# final.net
KiCad netlist of a schematic drawn in EAGLE
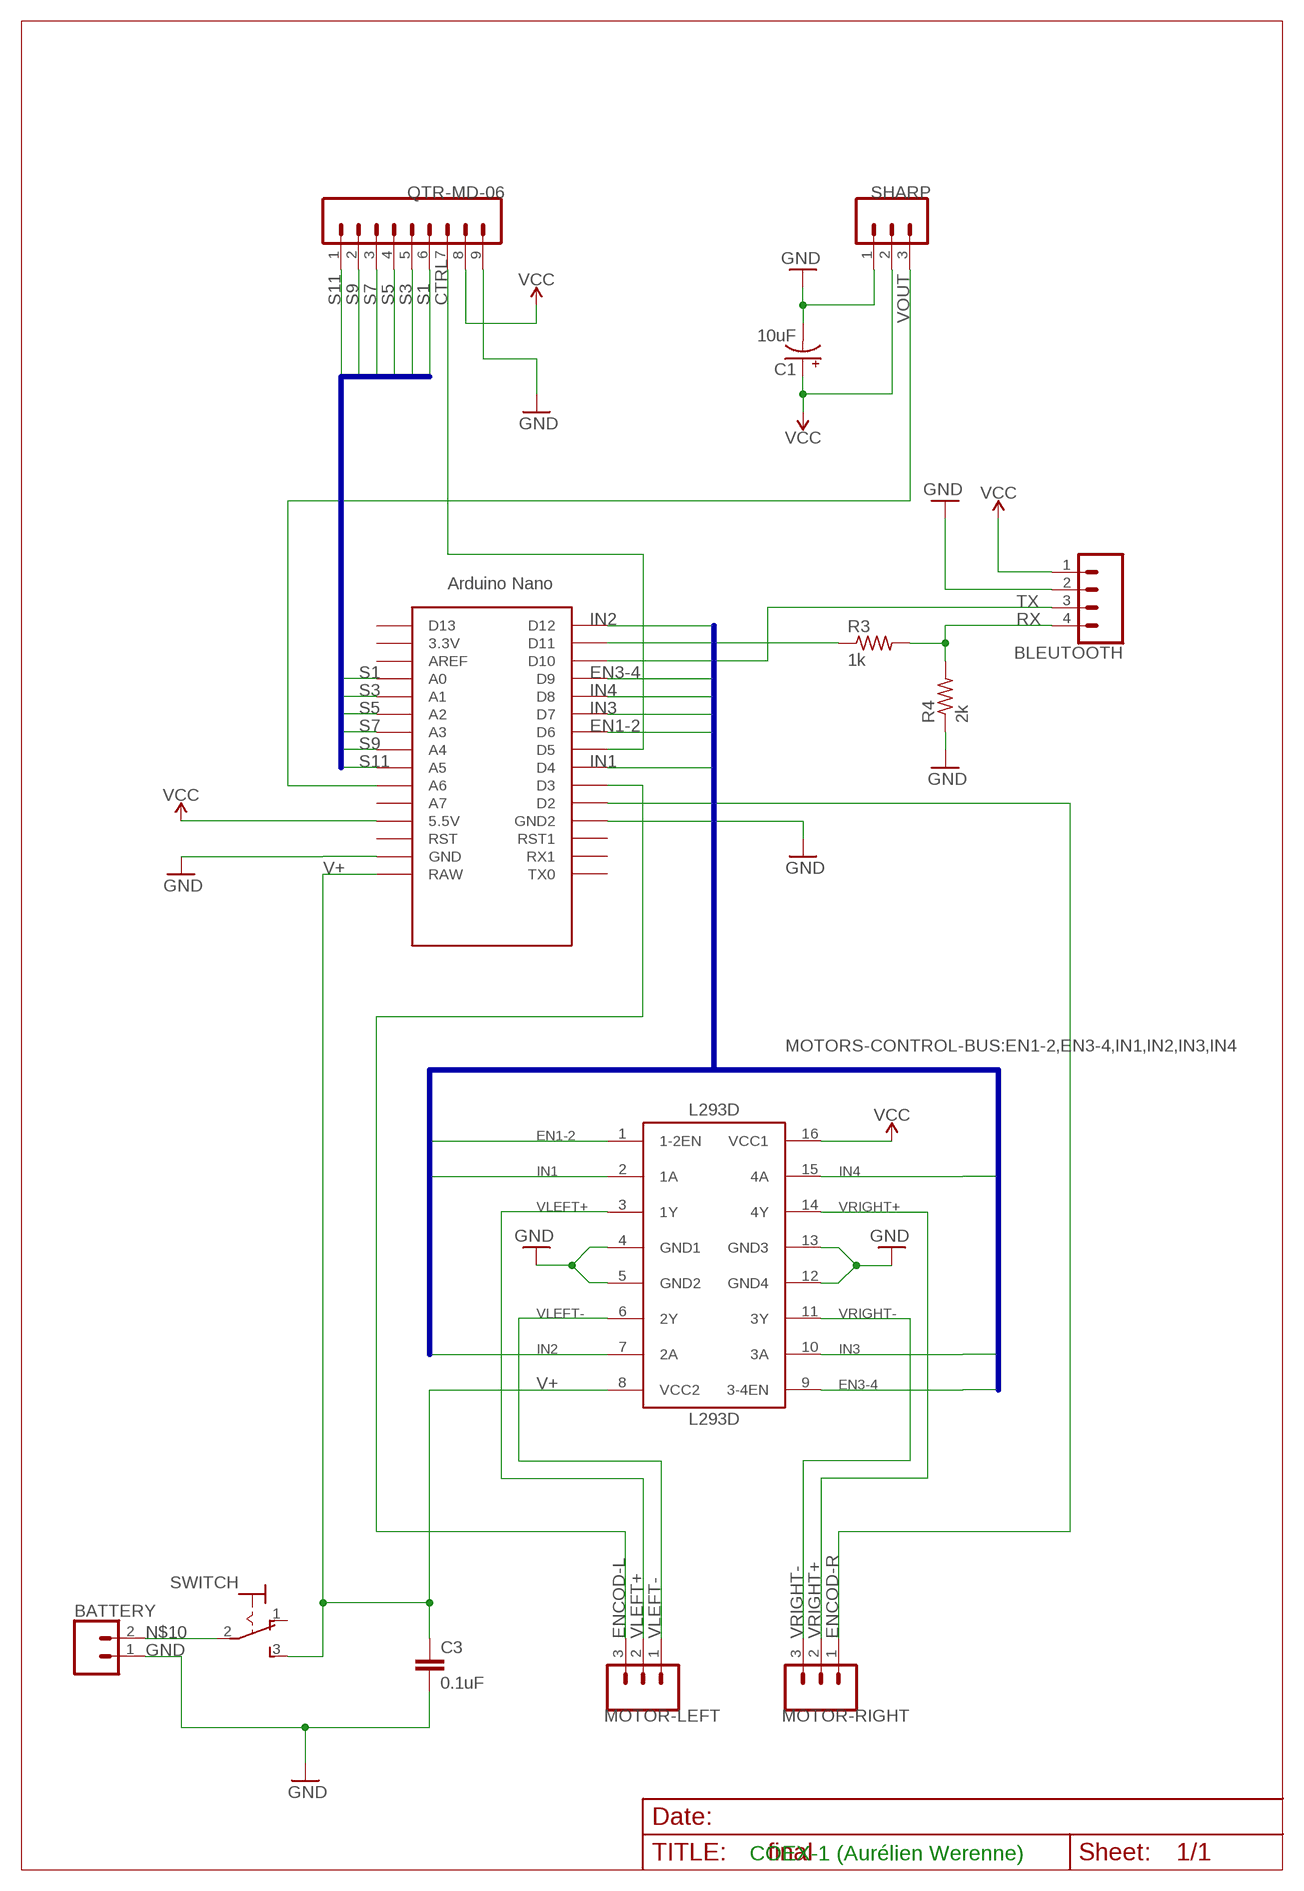
[diagram p0: schematic, sheet 1]

(export (version "E")
  (design (tool "Eeschema 10.0.6"))
  (components
    (comp (ref "BATTERY")
      (value "CONN_02")
      (footprint "eagle-import:1X02")
      (libsource (lib "eagle-import") (part "CONN_02"))
    )
    (comp (ref "BLEUTOOTH")
      (value "CONN_04")
      (footprint "eagle-import:1X04")
      (libsource (lib "eagle-import") (part "CONN_04"))
    )
    (comp (ref "C1")
      (value "10uF")
      (footprint "eagle-import:CPOL-RADIAL-2.5MM-5MM")
      (libsource (lib "eagle-import") (part "10UF-POLAR-RADIAL-2.5MM-25V-20%"))
    )
    (comp (ref "C3")
      (value "0.1uF")
      (footprint "eagle-import:CAP-PTH-SMALL-KIT")
      (libsource (lib "eagle-import") (part "0.1UF-KIT-EZ-50V-20%"))
    )
    (comp (ref "L293D")
      (value "L293D")
      (footprint "eagle-import:DIL16")
      (libsource (lib "eagle-import") (part "L293D"))
    )
    (comp (ref "MOTOR-LEFT")
      (value "CONN_03")
      (footprint "eagle-import:1X03")
      (libsource (lib "eagle-import") (part "CONN_03"))
    )
    (comp (ref "MOTOR-RIGHT")
      (value "CONN_03")
      (footprint "eagle-import:1X03")
      (libsource (lib "eagle-import") (part "CONN_03"))
    )
    (comp (ref "QTR-MD-06")
      (value "CONN_09")
      (footprint "eagle-import:1X09")
      (libsource (lib "eagle-import") (part "CONN_09"))
    )
    (comp (ref "R3")
      (value "1k")
      (footprint "eagle-import:0207_12")
      (libsource (lib "eagle-import") (part "R-US_0207/12"))
    )
    (comp (ref "R4")
      (value "2k")
      (footprint "eagle-import:0207_12")
      (libsource (lib "eagle-import") (part "R-US_0207/12"))
    )
    (comp (ref "SHARP")
      (value "CONN_03")
      (footprint "eagle-import:1X03")
      (libsource (lib "eagle-import") (part "CONN_03"))
    )
    (comp (ref "SWITCH")
      (value "320-916")
      (footprint "eagle-import:320-916")
      (libsource (lib "eagle-import") (part "320-916"))
    )
    (comp (ref "U$1")
      (value "NANO")
      (footprint "eagle-import:NANO")
      (libsource (lib "eagle-import") (part "NANO"))
    )
  )
  (nets
    (net (code "2") (name "/CTRL") (class "Default")
      (node (ref "QTR-MD-06") (pin "7") (pinfunction "7_7") (pintype "passive"))
      (node (ref "U$1") (pin "D5") (pinfunction "D5_D5") (pintype "bidirectional"))
    )
    (net (code "3") (name "/EN1-2") (class "Default")
      (node (ref "L293D") (pin "1") (pinfunction "1-2EN_1") (pintype "input"))
      (node (ref "U$1") (pin "D6") (pinfunction "D6_D6") (pintype "bidirectional"))
    )
    (net (code "4") (name "/EN3-4") (class "Default")
      (node (ref "L293D") (pin "9") (pinfunction "3-4EN_9") (pintype "input"))
      (node (ref "U$1") (pin "D9") (pinfunction "D9_D9") (pintype "bidirectional"))
    )
    (net (code "5") (name "/ENCOD-L") (class "Default")
      (node (ref "MOTOR-LEFT") (pin "3") (pinfunction "3_3") (pintype "passive"))
      (node (ref "U$1") (pin "D3") (pinfunction "D3_D3") (pintype "bidirectional"))
    )
    (net (code "6") (name "/ENCOD-R") (class "Default")
      (node (ref "MOTOR-RIGHT") (pin "1") (pinfunction "1_1") (pintype "passive"))
      (node (ref "U$1") (pin "D2") (pinfunction "D2_D2") (pintype "bidirectional"))
    )
    (net (code "7") (name "/IN1") (class "Default")
      (node (ref "L293D") (pin "2") (pinfunction "1A_2") (pintype "input"))
      (node (ref "U$1") (pin "D4") (pinfunction "D4_D4") (pintype "bidirectional"))
    )
    (net (code "8") (name "/IN2") (class "Default")
      (node (ref "L293D") (pin "7") (pinfunction "2A_7") (pintype "input"))
      (node (ref "U$1") (pin "D12") (pinfunction "D12_D12") (pintype "bidirectional"))
    )
    (net (code "9") (name "/IN3") (class "Default")
      (node (ref "L293D") (pin "10") (pinfunction "3A_10") (pintype "input"))
      (node (ref "U$1") (pin "D7") (pinfunction "D7_D7") (pintype "bidirectional"))
    )
    (net (code "10") (name "/IN4") (class "Default")
      (node (ref "L293D") (pin "15") (pinfunction "4A_15") (pintype "input"))
      (node (ref "U$1") (pin "D8") (pinfunction "D8_D8") (pintype "bidirectional"))
    )
    (net (code "11") (name "/N$10") (class "Default")
      (node (ref "BATTERY") (pin "2") (pinfunction "2_2") (pintype "passive"))
      (node (ref "SWITCH") (pin "2") (pinfunction "P_2") (pintype "passive"))
    )
    (net (code "12") (name "/RX") (class "Default")
      (node (ref "BLEUTOOTH") (pin "4") (pinfunction "4_4") (pintype "passive"))
      (node (ref "R3") (pin "2") (pinfunction "2_2") (pintype "passive"))
      (node (ref "R4") (pin "2") (pinfunction "2_2") (pintype "passive"))
    )
    (net (code "13") (name "/S1") (class "Default")
      (node (ref "QTR-MD-06") (pin "6") (pinfunction "6_6") (pintype "passive"))
      (node (ref "U$1") (pin "A0") (pinfunction "A0_A0") (pintype "bidirectional"))
    )
    (net (code "14") (name "/S3") (class "Default")
      (node (ref "QTR-MD-06") (pin "5") (pinfunction "5_5") (pintype "passive"))
      (node (ref "U$1") (pin "A1") (pinfunction "A1_A1") (pintype "bidirectional"))
    )
    (net (code "15") (name "/S5") (class "Default")
      (node (ref "QTR-MD-06") (pin "4") (pinfunction "4_4") (pintype "passive"))
      (node (ref "U$1") (pin "A2") (pinfunction "A2_A2") (pintype "bidirectional"))
    )
    (net (code "16") (name "/S7") (class "Default")
      (node (ref "QTR-MD-06") (pin "3") (pinfunction "3_3") (pintype "passive"))
      (node (ref "U$1") (pin "A3") (pinfunction "A3_A3") (pintype "bidirectional"))
    )
    (net (code "17") (name "/S9") (class "Default")
      (node (ref "QTR-MD-06") (pin "2") (pinfunction "2_2") (pintype "passive"))
      (node (ref "U$1") (pin "A4") (pinfunction "A4_A4") (pintype "bidirectional"))
    )
    (net (code "18") (name "/S11") (class "Default")
      (node (ref "QTR-MD-06") (pin "1") (pinfunction "1_1") (pintype "passive"))
      (node (ref "U$1") (pin "A5") (pinfunction "A5_A5") (pintype "bidirectional"))
    )
    (net (code "19") (name "/TX") (class "Default")
      (node (ref "BLEUTOOTH") (pin "3") (pinfunction "3_3") (pintype "passive"))
      (node (ref "U$1") (pin "D10") (pinfunction "D10_D10") (pintype "bidirectional"))
    )
    (net (code "20") (name "/V+") (class "Default")
      (node (ref "C3") (pin "1") (pinfunction "1_1") (pintype "passive"))
      (node (ref "L293D") (pin "8") (pinfunction "VCC2_8") (pintype "power_in"))
      (node (ref "SWITCH") (pin "3") (pinfunction "S_3") (pintype "passive"))
      (node (ref "U$1") (pin "RAW") (pinfunction "RAW_RAW") (pintype "bidirectional"))
    )
    (net (code "21") (name "/VLEFT+") (class "Default")
      (node (ref "L293D") (pin "3") (pinfunction "1Y_3") (pintype "output"))
      (node (ref "MOTOR-LEFT") (pin "2") (pinfunction "2_2") (pintype "passive"))
    )
    (net (code "22") (name "/VLEFT-") (class "Default")
      (node (ref "L293D") (pin "6") (pinfunction "2Y_6") (pintype "output"))
      (node (ref "MOTOR-LEFT") (pin "1") (pinfunction "1_1") (pintype "passive"))
    )
    (net (code "23") (name "/VOUT") (class "Default")
      (node (ref "SHARP") (pin "3") (pinfunction "3_3") (pintype "passive"))
      (node (ref "U$1") (pin "A6") (pinfunction "A6_A6") (pintype "bidirectional"))
    )
    (net (code "24") (name "/VRIGHT+") (class "Default")
      (node (ref "L293D") (pin "14") (pinfunction "4Y_14") (pintype "output"))
      (node (ref "MOTOR-RIGHT") (pin "2") (pinfunction "2_2") (pintype "passive"))
    )
    (net (code "25") (name "/VRIGHT-") (class "Default")
      (node (ref "L293D") (pin "11") (pinfunction "3Y_11") (pintype "output"))
      (node (ref "MOTOR-RIGHT") (pin "3") (pinfunction "3_3") (pintype "passive"))
    )
    (net (code "27") (name "GND") (class "Default")
      (node (ref "BATTERY") (pin "1") (pinfunction "1_1") (pintype "passive"))
      (node (ref "BLEUTOOTH") (pin "2") (pinfunction "2_2") (pintype "passive"))
      (node (ref "C1") (pin "2") (pinfunction "-_2") (pintype "passive"))
      (node (ref "C3") (pin "2") (pinfunction "2_2") (pintype "passive"))
      (node (ref "L293D") (pin "12") (pinfunction "GND4_12") (pintype "power_in"))
      (node (ref "L293D") (pin "13") (pinfunction "GND3_13") (pintype "power_in"))
      (node (ref "L293D") (pin "4") (pinfunction "GND1_4") (pintype "power_in"))
      (node (ref "L293D") (pin "5") (pinfunction "GND2_5") (pintype "power_in"))
      (node (ref "QTR-MD-06") (pin "9") (pinfunction "9_9") (pintype "passive"))
      (node (ref "R4") (pin "1") (pinfunction "1_1") (pintype "passive"))
      (node (ref "SHARP") (pin "1") (pinfunction "1_1") (pintype "passive"))
      (node (ref "U$1") (pin "GND") (pinfunction "GND_GND") (pintype "bidirectional"))
      (node (ref "U$1") (pin "GND1") (pinfunction "GND2_GND1") (pintype "bidirectional"))
    )
    (net (code "28") (name "Net-(R3-Pad1)") (class "Default")
      (node (ref "R3") (pin "1") (pinfunction "1_1") (pintype "passive"))
      (node (ref "U$1") (pin "D11") (pinfunction "D11_D11") (pintype "bidirectional"))
    )
    (net (code "29") (name "VCC") (class "Default")
      (node (ref "BLEUTOOTH") (pin "1") (pinfunction "1_1") (pintype "passive"))
      (node (ref "C1") (pin "1") (pinfunction "+_1") (pintype "passive"))
      (node (ref "L293D") (pin "16") (pinfunction "VCC1_16") (pintype "power_in"))
      (node (ref "QTR-MD-06") (pin "8") (pinfunction "8_8") (pintype "passive"))
      (node (ref "SHARP") (pin "2") (pinfunction "2_2") (pintype "passive"))
      (node (ref "U$1") (pin "5V") (pinfunction "5.5V_5V") (pintype "bidirectional"))
    )
    (net (code "30") (name "unconnected-(SWITCH-O-Pad1)") (class "Default")
      (node (ref "SWITCH") (pin "1") (pinfunction "O_1") (pintype "passive"))
    )
    (net (code "31") (name "unconnected-(U$1-Pad3.3V)") (class "Default")
      (node (ref "U$1") (pin "3.3V") (pinfunction "3.3V_3.3V") (pintype "bidirectional"))
    )
    (net (code "32") (name "unconnected-(U$1-PadA7)") (class "Default")
      (node (ref "U$1") (pin "A7") (pinfunction "A7_A7") (pintype "bidirectional"))
    )
    (net (code "33") (name "unconnected-(U$1-PadAREF)") (class "Default")
      (node (ref "U$1") (pin "AREF") (pinfunction "AREF_AREF") (pintype "bidirectional"))
    )
    (net (code "34") (name "unconnected-(U$1-PadD13)") (class "Default")
      (node (ref "U$1") (pin "D13") (pinfunction "D13_D13") (pintype "bidirectional"))
    )
    (net (code "35") (name "unconnected-(U$1-PadICSP1)") (class "Default")
      (node (ref "U$1") (pin "ICSP1") (pinfunction "ICSP1_ICSP1") (pintype "bidirectional"))
    )
    (net (code "36") (name "unconnected-(U$1-PadICSP2)") (class "Default")
      (node (ref "U$1") (pin "ICSP2") (pinfunction "ICSP2_ICSP2") (pintype "bidirectional"))
    )
    (net (code "37") (name "unconnected-(U$1-PadICSP3)") (class "Default")
      (node (ref "U$1") (pin "ICSP3") (pinfunction "ICSP3_ICSP3") (pintype "bidirectional"))
    )
    (net (code "38") (name "unconnected-(U$1-PadICSP4)") (class "Default")
      (node (ref "U$1") (pin "ICSP4") (pinfunction "ICSP4_ICSP4") (pintype "bidirectional"))
    )
    (net (code "39") (name "unconnected-(U$1-PadICSP5)") (class "Default")
      (node (ref "U$1") (pin "ICSP5") (pinfunction "ICSP5_ICSP5") (pintype "bidirectional"))
    )
    (net (code "40") (name "unconnected-(U$1-PadICSP6)") (class "Default")
      (node (ref "U$1") (pin "ICSP6") (pinfunction "ICSP6_ICSP6") (pintype "bidirectional"))
    )
    (net (code "41") (name "unconnected-(U$1-PadRST)") (class "Default")
      (node (ref "U$1") (pin "RST") (pinfunction "RST_RST") (pintype "bidirectional"))
    )
    (net (code "42") (name "unconnected-(U$1-PadRST1)") (class "Default")
      (node (ref "U$1") (pin "RST1") (pinfunction "RST1_RST1") (pintype "bidirectional"))
    )
    (net (code "43") (name "unconnected-(U$1-PadRX1)") (class "Default")
      (node (ref "U$1") (pin "RX1") (pinfunction "RX1_RX1") (pintype "bidirectional"))
    )
    (net (code "44") (name "unconnected-(U$1-PadTX0)") (class "Default")
      (node (ref "U$1") (pin "TX0") (pinfunction "TX0_TX0") (pintype "bidirectional"))
    )
  )
)
